# field_rotator.net
KiCad netlist of a schematic drawn in EAGLE
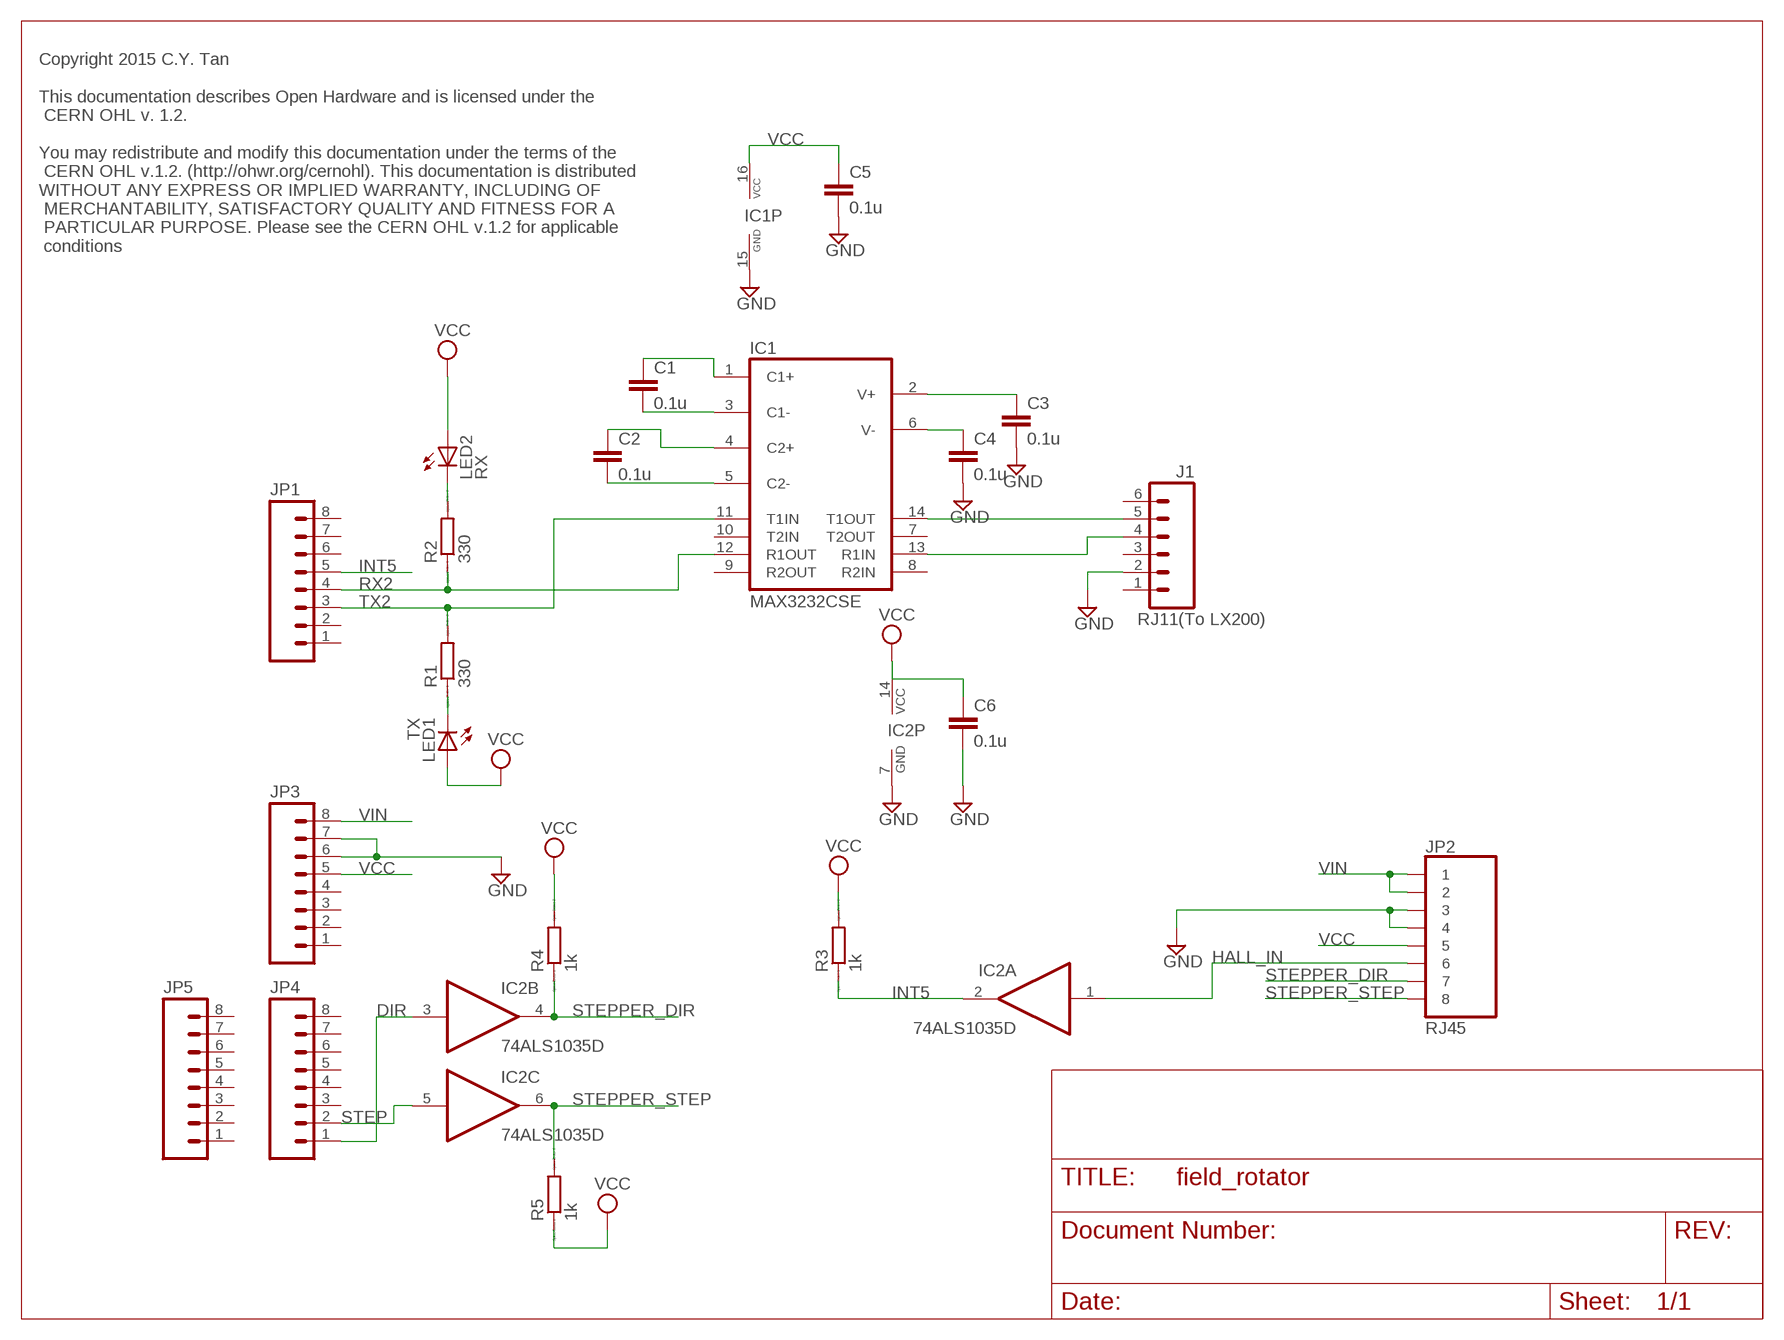
[diagram p0: schematic, sheet 1]

(export (version "E")
  (design (tool "Eeschema 10.0.6"))
  (components
    (comp (ref "C1")
      (value "0.1u")
      (footprint "eagle-import:C1206")
      (libsource (lib "eagle-import") (part "C-EUC1206"))
    )
    (comp (ref "C2")
      (value "0.1u")
      (footprint "eagle-import:C1206")
      (libsource (lib "eagle-import") (part "C-EUC1206"))
    )
    (comp (ref "C3")
      (value "0.1u")
      (footprint "eagle-import:C1206")
      (libsource (lib "eagle-import") (part "C-EUC1206"))
    )
    (comp (ref "C4")
      (value "0.1u")
      (footprint "eagle-import:C1206")
      (libsource (lib "eagle-import") (part "C-EUC1206"))
    )
    (comp (ref "C5")
      (value "0.1u")
      (footprint "eagle-import:C1206")
      (libsource (lib "eagle-import") (part "C-EUC1206"))
    )
    (comp (ref "C6")
      (value "0.1u")
      (footprint "eagle-import:C1206")
      (libsource (lib "eagle-import") (part "C-EUC1206"))
    )
    (comp (ref "IC1")
      (value "MAX3232CSE")
      (footprint "eagle-import:SO16")
      (libsource (lib "eagle-import") (part "MAX3232SEC"))
    )
    (comp (ref "IC2")
      (value "74ALS1035D")
      (footprint "eagle-import:SO14")
      (libsource (lib "eagle-import") (part "74ALS1035D"))
    )
    (comp (ref "J1")
      (value "RJ11(To LX200)")
      (footprint "eagle-import:RJ11-6")
      (libsource (lib "eagle-import") (part "RJ11-6PTH"))
    )
    (comp (ref "JP1")
      (value "M08SILK_FEMALE_PTH")
      (footprint "eagle-import:1X08")
      (libsource (lib "eagle-import") (part "M08SILK_FEMALE_PTH"))
    )
    (comp (ref "JP2")
      (value "RJ45")
      (footprint "eagle-import:RJ45-8")
      (libsource (lib "eagle-import") (part "RJ45-8PTH"))
    )
    (comp (ref "JP3")
      (value "M08SILK_FEMALE_PTH")
      (footprint "eagle-import:1X08")
      (libsource (lib "eagle-import") (part "M08SILK_FEMALE_PTH"))
    )
    (comp (ref "JP4")
      (value "M08SILK_FEMALE_PTH")
      (footprint "eagle-import:1X08")
      (libsource (lib "eagle-import") (part "M08SILK_FEMALE_PTH"))
    )
    (comp (ref "JP5")
      (value "M08SILK_FEMALE_PTH")
      (footprint "eagle-import:1X08")
      (libsource (lib "eagle-import") (part "M08SILK_FEMALE_PTH"))
    )
    (comp (ref "LED1")
      (value "TX")
      (footprint "eagle-import:CHIPLED_1206")
      (libsource (lib "eagle-import") (part "LEDCHIPLED_1206"))
    )
    (comp (ref "LED2")
      (value "RX")
      (footprint "eagle-import:CHIPLED_1206")
      (libsource (lib "eagle-import") (part "LEDCHIPLED_1206"))
    )
    (comp (ref "R1")
      (value "330")
      (footprint "eagle-import:R0805")
      (libsource (lib "eagle-import") (part "R"))
    )
    (comp (ref "R2")
      (value "330")
      (footprint "eagle-import:R0805")
      (libsource (lib "eagle-import") (part "R"))
    )
    (comp (ref "R3")
      (value "1k")
      (footprint "eagle-import:R0805")
      (libsource (lib "eagle-import") (part "R"))
    )
    (comp (ref "R4")
      (value "1k")
      (footprint "eagle-import:R0805")
      (libsource (lib "eagle-import") (part "R"))
    )
    (comp (ref "R5")
      (value "1k")
      (footprint "eagle-import:R0805")
      (libsource (lib "eagle-import") (part "R"))
    )
  )
  (nets
    (net (code "1") (name "/DIR") (class "Default")
      (node (ref "IC2") (pin "3") (pinfunction "I_3") (pintype "input"))
      (node (ref "JP4") (pin "1") (pinfunction "1_1") (pintype "passive"))
    )
    (net (code "2") (name "/HALL_IN") (class "Default")
      (node (ref "IC2") (pin "1") (pinfunction "I_1") (pintype "input"))
      (node (ref "JP2") (pin "6") (pinfunction "6_6") (pintype "bidirectional"))
    )
    (net (code "3") (name "/INT5") (class "Default")
      (node (ref "IC2") (pin "2") (pinfunction "O_2") (pintype "open_collector"))
      (node (ref "JP1") (pin "5") (pinfunction "5_5") (pintype "passive"))
      (node (ref "R3") (pin "1") (pinfunction "1_1") (pintype "passive"))
    )
    (net (code "4") (name "/RX2") (class "Default")
      (node (ref "IC1") (pin "12") (pinfunction "R1OUT_12") (pintype "output"))
      (node (ref "JP1") (pin "4") (pinfunction "4_4") (pintype "passive"))
      (node (ref "R2") (pin "1") (pinfunction "1_1") (pintype "passive"))
    )
    (net (code "5") (name "/STEP") (class "Default")
      (node (ref "IC2") (pin "5") (pinfunction "I_5") (pintype "input"))
      (node (ref "JP4") (pin "2") (pinfunction "2_2") (pintype "passive"))
    )
    (net (code "6") (name "/STEPPER_DIR") (class "Default")
      (node (ref "IC2") (pin "4") (pinfunction "O_4") (pintype "open_collector"))
      (node (ref "JP2") (pin "7") (pinfunction "7_7") (pintype "bidirectional"))
      (node (ref "R4") (pin "1") (pinfunction "1_1") (pintype "passive"))
    )
    (net (code "7") (name "/STEPPER_STEP") (class "Default")
      (node (ref "IC2") (pin "6") (pinfunction "O_6") (pintype "open_collector"))
      (node (ref "JP2") (pin "8") (pinfunction "8_8") (pintype "bidirectional"))
      (node (ref "R5") (pin "2") (pinfunction "2_2") (pintype "passive"))
    )
    (net (code "8") (name "/TX2") (class "Default")
      (node (ref "IC1") (pin "11") (pinfunction "T1IN_11") (pintype "input"))
      (node (ref "JP1") (pin "3") (pinfunction "3_3") (pintype "passive"))
      (node (ref "R1") (pin "2") (pinfunction "2_2") (pintype "passive"))
    )
    (net (code "9") (name "/VIN") (class "Default")
      (node (ref "JP2") (pin "1") (pinfunction "1_1") (pintype "bidirectional"))
      (node (ref "JP2") (pin "2") (pinfunction "2_2") (pintype "bidirectional"))
      (node (ref "JP3") (pin "8") (pinfunction "8_8") (pintype "passive"))
    )
    (net (code "10") (name "GND") (class "Default")
      (node (ref "C3") (pin "2") (pinfunction "2_2") (pintype "passive"))
      (node (ref "C4") (pin "2") (pinfunction "2_2") (pintype "passive"))
      (node (ref "C5") (pin "2") (pinfunction "2_2") (pintype "passive"))
      (node (ref "C6") (pin "2") (pinfunction "2_2") (pintype "passive"))
      (node (ref "IC1") (pin "15") (pinfunction "GND_15") (pintype "power_in"))
      (node (ref "IC2") (pin "7") (pinfunction "GND_7") (pintype "power_in"))
      (node (ref "J1") (pin "2") (pinfunction "2_2") (pintype "passive"))
      (node (ref "JP2") (pin "3") (pinfunction "3_3") (pintype "bidirectional"))
      (node (ref "JP2") (pin "4") (pinfunction "4_4") (pintype "bidirectional"))
      (node (ref "JP3") (pin "6") (pinfunction "6_6") (pintype "passive"))
      (node (ref "JP3") (pin "7") (pinfunction "7_7") (pintype "passive"))
    )
    (net (code "11") (name "Net-(IC1A-C1+)") (class "Default")
      (node (ref "C1") (pin "1") (pinfunction "1_1") (pintype "passive"))
      (node (ref "IC1") (pin "1") (pinfunction "C1+_1") (pintype "bidirectional"))
    )
    (net (code "12") (name "Net-(IC1A-C1-)") (class "Default")
      (node (ref "C1") (pin "2") (pinfunction "2_2") (pintype "passive"))
      (node (ref "IC1") (pin "3") (pinfunction "C1-_3") (pintype "bidirectional"))
    )
    (net (code "13") (name "Net-(IC1A-C2+)") (class "Default")
      (node (ref "C2") (pin "1") (pinfunction "1_1") (pintype "passive"))
      (node (ref "IC1") (pin "4") (pinfunction "C2+_4") (pintype "bidirectional"))
    )
    (net (code "14") (name "Net-(IC1A-C2-)") (class "Default")
      (node (ref "C2") (pin "2") (pinfunction "2_2") (pintype "passive"))
      (node (ref "IC1") (pin "5") (pinfunction "C2-_5") (pintype "bidirectional"))
    )
    (net (code "15") (name "Net-(IC1A-R1IN)") (class "Default")
      (node (ref "IC1") (pin "13") (pinfunction "R1IN_13") (pintype "input"))
      (node (ref "J1") (pin "4") (pinfunction "4_4") (pintype "passive"))
    )
    (net (code "16") (name "Net-(IC1A-T1OUT)") (class "Default")
      (node (ref "IC1") (pin "14") (pinfunction "T1OUT_14") (pintype "output"))
      (node (ref "J1") (pin "5") (pinfunction "5_5") (pintype "passive"))
    )
    (net (code "17") (name "Net-(IC1A-V+)") (class "Default")
      (node (ref "C3") (pin "1") (pinfunction "1_1") (pintype "passive"))
      (node (ref "IC1") (pin "2") (pinfunction "V+_2") (pintype "bidirectional"))
    )
    (net (code "18") (name "Net-(IC1A-V-)") (class "Default")
      (node (ref "C4") (pin "1") (pinfunction "1_1") (pintype "passive"))
      (node (ref "IC1") (pin "6") (pinfunction "V-_6") (pintype "bidirectional"))
    )
    (net (code "19") (name "Net-(LED1-PadC)") (class "Default")
      (node (ref "LED1") (pin "C") (pinfunction "C_C") (pintype "passive"))
      (node (ref "R1") (pin "1") (pinfunction "1_1") (pintype "passive"))
    )
    (net (code "20") (name "Net-(LED2-PadC)") (class "Default")
      (node (ref "LED2") (pin "C") (pinfunction "C_C") (pintype "passive"))
      (node (ref "R2") (pin "2") (pinfunction "2_2") (pintype "passive"))
    )
    (net (code "21") (name "VCC") (class "Default")
      (node (ref "C5") (pin "1") (pinfunction "1_1") (pintype "passive"))
      (node (ref "C6") (pin "1") (pinfunction "1_1") (pintype "passive"))
      (node (ref "IC1") (pin "16") (pinfunction "VCC_16") (pintype "power_in"))
      (node (ref "IC2") (pin "14") (pinfunction "VCC_14") (pintype "power_in"))
      (node (ref "JP2") (pin "5") (pinfunction "5_5") (pintype "bidirectional"))
      (node (ref "JP3") (pin "5") (pinfunction "5_5") (pintype "passive"))
      (node (ref "LED1") (pin "A") (pinfunction "A_A") (pintype "passive"))
      (node (ref "LED2") (pin "A") (pinfunction "A_A") (pintype "passive"))
      (node (ref "R3") (pin "2") (pinfunction "2_2") (pintype "passive"))
      (node (ref "R4") (pin "2") (pinfunction "2_2") (pintype "passive"))
      (node (ref "R5") (pin "1") (pinfunction "1_1") (pintype "passive"))
    )
    (net (code "22") (name "unconnected-(IC1A-R2IN-Pad8)") (class "Default")
      (node (ref "IC1") (pin "8") (pinfunction "R2IN_8") (pintype "input"))
    )
    (net (code "23") (name "unconnected-(IC1A-R2OUT-Pad9)") (class "Default")
      (node (ref "IC1") (pin "9") (pinfunction "R2OUT_9") (pintype "output"))
    )
    (net (code "24") (name "unconnected-(IC1A-T2IN-Pad10)") (class "Default")
      (node (ref "IC1") (pin "10") (pinfunction "T2IN_10") (pintype "input"))
    )
    (net (code "25") (name "unconnected-(IC1A-T2OUT-Pad7)") (class "Default")
      (node (ref "IC1") (pin "7") (pinfunction "T2OUT_7") (pintype "output"))
    )
    (net (code "26") (name "unconnected-(J1-Pad1)") (class "Default")
      (node (ref "J1") (pin "1") (pinfunction "1_1") (pintype "passive"))
    )
    (net (code "27") (name "unconnected-(J1-Pad3)") (class "Default")
      (node (ref "J1") (pin "3") (pinfunction "3_3") (pintype "passive"))
    )
    (net (code "28") (name "unconnected-(J1-Pad6)") (class "Default")
      (node (ref "J1") (pin "6") (pinfunction "6_6") (pintype "passive"))
    )
    (net (code "29") (name "unconnected-(JP1-Pad1)") (class "Default")
      (node (ref "JP1") (pin "1") (pinfunction "1_1") (pintype "passive"))
    )
    (net (code "30") (name "unconnected-(JP1-Pad2)") (class "Default")
      (node (ref "JP1") (pin "2") (pinfunction "2_2") (pintype "passive"))
    )
    (net (code "31") (name "unconnected-(JP1-Pad6)") (class "Default")
      (node (ref "JP1") (pin "6") (pinfunction "6_6") (pintype "passive"))
    )
    (net (code "32") (name "unconnected-(JP1-Pad7)") (class "Default")
      (node (ref "JP1") (pin "7") (pinfunction "7_7") (pintype "passive"))
    )
    (net (code "33") (name "unconnected-(JP1-Pad8)") (class "Default")
      (node (ref "JP1") (pin "8") (pinfunction "8_8") (pintype "passive"))
    )
    (net (code "34") (name "unconnected-(JP3-Pad1)") (class "Default")
      (node (ref "JP3") (pin "1") (pinfunction "1_1") (pintype "passive"))
    )
    (net (code "35") (name "unconnected-(JP3-Pad2)") (class "Default")
      (node (ref "JP3") (pin "2") (pinfunction "2_2") (pintype "passive"))
    )
    (net (code "36") (name "unconnected-(JP3-Pad3)") (class "Default")
      (node (ref "JP3") (pin "3") (pinfunction "3_3") (pintype "passive"))
    )
    (net (code "37") (name "unconnected-(JP3-Pad4)") (class "Default")
      (node (ref "JP3") (pin "4") (pinfunction "4_4") (pintype "passive"))
    )
    (net (code "38") (name "unconnected-(JP4-Pad3)") (class "Default")
      (node (ref "JP4") (pin "3") (pinfunction "3_3") (pintype "passive"))
    )
    (net (code "39") (name "unconnected-(JP4-Pad4)") (class "Default")
      (node (ref "JP4") (pin "4") (pinfunction "4_4") (pintype "passive"))
    )
    (net (code "40") (name "unconnected-(JP4-Pad5)") (class "Default")
      (node (ref "JP4") (pin "5") (pinfunction "5_5") (pintype "passive"))
    )
    (net (code "41") (name "unconnected-(JP4-Pad6)") (class "Default")
      (node (ref "JP4") (pin "6") (pinfunction "6_6") (pintype "passive"))
    )
    (net (code "42") (name "unconnected-(JP4-Pad7)") (class "Default")
      (node (ref "JP4") (pin "7") (pinfunction "7_7") (pintype "passive"))
    )
    (net (code "43") (name "unconnected-(JP4-Pad8)") (class "Default")
      (node (ref "JP4") (pin "8") (pinfunction "8_8") (pintype "passive"))
    )
    (net (code "44") (name "unconnected-(JP5-Pad1)") (class "Default")
      (node (ref "JP5") (pin "1") (pinfunction "1_1") (pintype "passive"))
    )
    (net (code "45") (name "unconnected-(JP5-Pad2)") (class "Default")
      (node (ref "JP5") (pin "2") (pinfunction "2_2") (pintype "passive"))
    )
    (net (code "46") (name "unconnected-(JP5-Pad3)") (class "Default")
      (node (ref "JP5") (pin "3") (pinfunction "3_3") (pintype "passive"))
    )
    (net (code "47") (name "unconnected-(JP5-Pad4)") (class "Default")
      (node (ref "JP5") (pin "4") (pinfunction "4_4") (pintype "passive"))
    )
    (net (code "48") (name "unconnected-(JP5-Pad5)") (class "Default")
      (node (ref "JP5") (pin "5") (pinfunction "5_5") (pintype "passive"))
    )
    (net (code "49") (name "unconnected-(JP5-Pad6)") (class "Default")
      (node (ref "JP5") (pin "6") (pinfunction "6_6") (pintype "passive"))
    )
    (net (code "50") (name "unconnected-(JP5-Pad7)") (class "Default")
      (node (ref "JP5") (pin "7") (pinfunction "7_7") (pintype "passive"))
    )
    (net (code "51") (name "unconnected-(JP5-Pad8)") (class "Default")
      (node (ref "JP5") (pin "8") (pinfunction "8_8") (pintype "passive"))
    )
  )
)
